# Plat10con.net
KiCad netlist of a schematic drawn in EAGLE
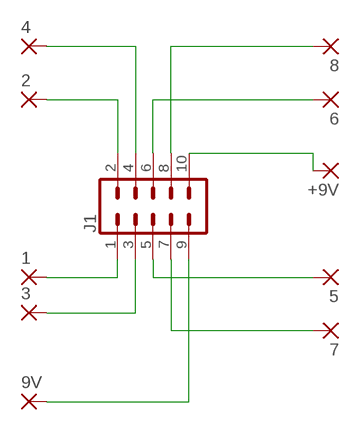
[diagram p0: schematic, sheet 1]

(export (version "E")
  (design (tool "Eeschema 10.0.6"))
  (components
    (comp (ref "+9V")
      (value "1,6/0,9")
      (footprint "eagle-import:1,6_0,9")
      (libsource (lib "eagle-import") (part "1,6/0,9"))
    )
    (comp (ref "1")
      (value "1,6/0,9")
      (footprint "eagle-import:1,6_0,9")
      (libsource (lib "eagle-import") (part "1,6/0,9"))
    )
    (comp (ref "2")
      (value "1,6/0,9")
      (footprint "eagle-import:1,6_0,9")
      (libsource (lib "eagle-import") (part "1,6/0,9"))
    )
    (comp (ref "3")
      (value "1,6/0,9")
      (footprint "eagle-import:1,6_0,9")
      (libsource (lib "eagle-import") (part "1,6/0,9"))
    )
    (comp (ref "4")
      (value "1,6/0,9")
      (footprint "eagle-import:1,6_0,9")
      (libsource (lib "eagle-import") (part "1,6/0,9"))
    )
    (comp (ref "5")
      (value "1,6/0,9")
      (footprint "eagle-import:1,6_0,9")
      (libsource (lib "eagle-import") (part "1,6/0,9"))
    )
    (comp (ref "6")
      (value "1,6/0,9")
      (footprint "eagle-import:1,6_0,9")
      (libsource (lib "eagle-import") (part "1,6/0,9"))
    )
    (comp (ref "7")
      (value "1,6/0,9")
      (footprint "eagle-import:1,6_0,9")
      (libsource (lib "eagle-import") (part "1,6/0,9"))
    )
    (comp (ref "8")
      (value "1,6/0,9")
      (footprint "eagle-import:1,6_0,9")
      (libsource (lib "eagle-import") (part "1,6/0,9"))
    )
    (comp (ref "9V")
      (value "1,6/0,9")
      (footprint "eagle-import:1,6_0,9")
      (libsource (lib "eagle-import") (part "1,6/0,9"))
    )
    (comp (ref "J1")
      (value "CONN_05X2SHD")
      (footprint "eagle-import:2X5-SHROUDED")
      (libsource (lib "eagle-import") (part "CONN_05X2SHD"))
    )
  )
  (nets
    (net (code "1") (name "Net-(+9V-P)") (class "Default")
      (node (ref "+9V") (pin "1") (pinfunction "P_1") (pintype "passive"))
      (node (ref "J1") (pin "10") (pinfunction "10_10") (pintype "passive"))
    )
    (net (code "2") (name "Net-(1-P)") (class "Default")
      (node (ref "1") (pin "1") (pinfunction "P_1") (pintype "passive"))
      (node (ref "J1") (pin "1") (pinfunction "1_1") (pintype "passive"))
    )
    (net (code "3") (name "Net-(2-P)") (class "Default")
      (node (ref "2") (pin "1") (pinfunction "P_1") (pintype "passive"))
      (node (ref "J1") (pin "2") (pinfunction "2_2") (pintype "passive"))
    )
    (net (code "4") (name "Net-(3-P)") (class "Default")
      (node (ref "3") (pin "1") (pinfunction "P_1") (pintype "passive"))
      (node (ref "J1") (pin "3") (pinfunction "3_3") (pintype "passive"))
    )
    (net (code "5") (name "Net-(4-P)") (class "Default")
      (node (ref "4") (pin "1") (pinfunction "P_1") (pintype "passive"))
      (node (ref "J1") (pin "4") (pinfunction "4_4") (pintype "passive"))
    )
    (net (code "6") (name "Net-(5-P)") (class "Default")
      (node (ref "5") (pin "1") (pinfunction "P_1") (pintype "passive"))
      (node (ref "J1") (pin "5") (pinfunction "5_5") (pintype "passive"))
    )
    (net (code "7") (name "Net-(6-P)") (class "Default")
      (node (ref "6") (pin "1") (pinfunction "P_1") (pintype "passive"))
      (node (ref "J1") (pin "6") (pinfunction "6_6") (pintype "passive"))
    )
    (net (code "8") (name "Net-(7-P)") (class "Default")
      (node (ref "7") (pin "1") (pinfunction "P_1") (pintype "passive"))
      (node (ref "J1") (pin "7") (pinfunction "7_7") (pintype "passive"))
    )
    (net (code "9") (name "Net-(8-P)") (class "Default")
      (node (ref "8") (pin "1") (pinfunction "P_1") (pintype "passive"))
      (node (ref "J1") (pin "8") (pinfunction "8_8") (pintype "passive"))
    )
    (net (code "10") (name "Net-(9V-P)") (class "Default")
      (node (ref "9V") (pin "1") (pinfunction "P_1") (pintype "passive"))
      (node (ref "J1") (pin "9") (pinfunction "9_9") (pintype "passive"))
    )
  )
)
